# top.net
KiCad netlist of a schematic drawn in Altium Designer
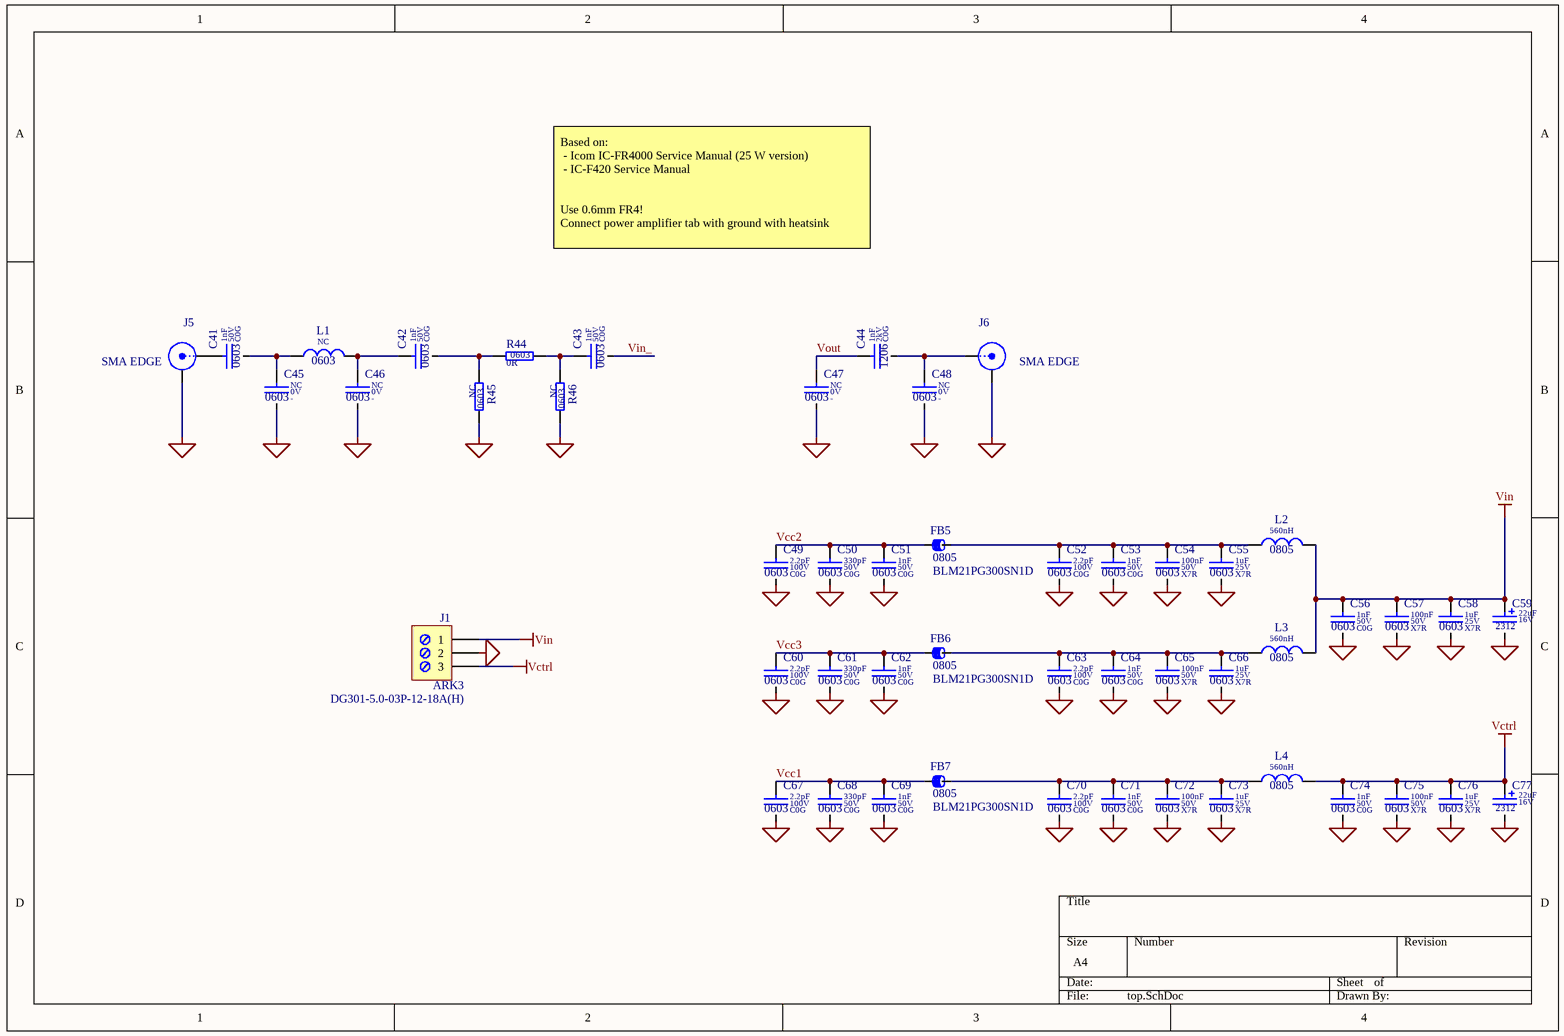
[diagram p0: top.SchDoc]

(export (version "E")
  (design (tool "Eeschema 10.0.6"))
  (components
    (comp (ref "C41")
      (value "1nF")
      (footprint "C_0603_1608")
      (description "Capacitor")
      (fields
        (field (name "DIELECTRIC") "C0G")
        (field (name "VOLTAGE") "50V")
        (field (name "SCH_FOOTPRINT") "0603")
        (field (name "PART NUMBER") "C_1nF_50V_C0G_0603_5")
        (field (name "MANUFACTURER") "Samsung")
      )
      (libsource (lib "Library") (part "C"))
    )
    (comp (ref "C42")
      (value "1nF")
      (footprint "C_0603_1608")
      (description "Capacitor")
      (fields
        (field (name "DIELECTRIC") "C0G")
        (field (name "VOLTAGE") "50V")
        (field (name "SCH_FOOTPRINT") "0603")
        (field (name "PART NUMBER") "C_1nF_50V_C0G_0603_5")
        (field (name "MANUFACTURER") "Samsung")
      )
      (libsource (lib "Library") (part "C"))
    )
    (comp (ref "C43")
      (value "1nF")
      (footprint "C_0603_1608")
      (description "Capacitor")
      (fields
        (field (name "DIELECTRIC") "C0G")
        (field (name "VOLTAGE") "50V")
        (field (name "SCH_FOOTPRINT") "0603")
        (field (name "PART NUMBER") "C_1nF_50V_C0G_0603_5")
        (field (name "MANUFACTURER") "Samsung")
      )
      (libsource (lib "Library") (part "C"))
    )
    (comp (ref "C44")
      (value "1nF")
      (footprint "C_1206_3216")
      (description "Capacitor")
      (fields
        (field (name "DIELECTRIC") "C0G")
        (field (name "VOLTAGE") "2kV")
        (field (name "SCH_FOOTPRINT") "1206")
        (field (name "PART NUMBER") "C_1nF_2kV_C0G_1206_10")
        (field (name "MANUFACTURER") "AVX")
      )
      (libsource (lib "Library") (part "C"))
    )
    (comp (ref "C45")
      (value "NC")
      (footprint "C_NC_0603_1608")
      (description "Capacitor")
      (fields
        (field (name "DIELECTRIC") "-")
        (field (name "VOLTAGE") "0V")
        (field (name "SCH_FOOTPRINT") "0603")
        (field (name "PART NUMBER") "C_GENERIC_0603")
      )
      (libsource (lib "Library") (part "C"))
    )
    (comp (ref "C46")
      (value "NC")
      (footprint "C_NC_0603_1608")
      (description "Capacitor")
      (fields
        (field (name "DIELECTRIC") "-")
        (field (name "VOLTAGE") "0V")
        (field (name "SCH_FOOTPRINT") "0603")
        (field (name "PART NUMBER") "C_GENERIC_0603")
      )
      (libsource (lib "Library") (part "C"))
    )
    (comp (ref "C47")
      (value "NC")
      (footprint "C_NC_0603_1608")
      (description "Capacitor")
      (fields
        (field (name "DIELECTRIC") "-")
        (field (name "VOLTAGE") "0V")
        (field (name "SCH_FOOTPRINT") "0603")
        (field (name "PART NUMBER") "C_GENERIC_0603")
      )
      (libsource (lib "Library") (part "C"))
    )
    (comp (ref "C48")
      (value "NC")
      (footprint "C_NC_0603_1608")
      (description "Capacitor")
      (fields
        (field (name "DIELECTRIC") "-")
        (field (name "VOLTAGE") "0V")
        (field (name "SCH_FOOTPRINT") "0603")
        (field (name "PART NUMBER") "C_GENERIC_0603")
      )
      (libsource (lib "Library") (part "C"))
    )
    (comp (ref "C49")
      (value "2.2pF")
      (footprint "C_0603_1608")
      (description "Capacitor")
      (fields
        (field (name "DIELECTRIC") "C0G")
        (field (name "VOLTAGE") "100V")
        (field (name "SCH_FOOTPRINT") "0603")
        (field (name "PART NUMBER") "C_2.2pF_100V_C0G_0603_5")
        (field (name "MANUFACTURER") "AVX")
      )
      (libsource (lib "Library") (part "C"))
    )
    (comp (ref "C50")
      (value "330pF")
      (footprint "C_0603_1608")
      (description "Capacitor")
      (fields
        (field (name "DIELECTRIC") "C0G")
        (field (name "VOLTAGE") "50V")
        (field (name "SCH_FOOTPRINT") "0603")
        (field (name "PART NUMBER") "C_330pF_50V_C0G_0603_5")
        (field (name "MANUFACTURER") "Murata")
      )
      (libsource (lib "Library") (part "C"))
    )
    (comp (ref "C51")
      (value "1nF")
      (footprint "C_0603_1608")
      (description "Capacitor")
      (fields
        (field (name "DIELECTRIC") "C0G")
        (field (name "VOLTAGE") "50V")
        (field (name "SCH_FOOTPRINT") "0603")
        (field (name "PART NUMBER") "C_1nF_50V_C0G_0603_5")
        (field (name "MANUFACTURER") "Samsung")
      )
      (libsource (lib "Library") (part "C"))
    )
    (comp (ref "C52")
      (value "2.2pF")
      (footprint "C_0603_1608")
      (description "Capacitor")
      (fields
        (field (name "DIELECTRIC") "C0G")
        (field (name "VOLTAGE") "100V")
        (field (name "SCH_FOOTPRINT") "0603")
        (field (name "PART NUMBER") "C_2.2pF_100V_C0G_0603_5")
        (field (name "MANUFACTURER") "AVX")
      )
      (libsource (lib "Library") (part "C"))
    )
    (comp (ref "C53")
      (value "1nF")
      (footprint "C_0603_1608")
      (description "Capacitor")
      (fields
        (field (name "DIELECTRIC") "C0G")
        (field (name "VOLTAGE") "50V")
        (field (name "SCH_FOOTPRINT") "0603")
        (field (name "PART NUMBER") "C_1nF_50V_C0G_0603_5")
        (field (name "MANUFACTURER") "Samsung")
      )
      (libsource (lib "Library") (part "C"))
    )
    (comp (ref "C54")
      (value "100nF")
      (footprint "C_0603_1608")
      (description "Capacitor")
      (fields
        (field (name "DIELECTRIC") "X7R")
        (field (name "VOLTAGE") "50V")
        (field (name "SCH_FOOTPRINT") "0603")
        (field (name "PART NUMBER") "C_100nF_50V_X7R_0603_5")
        (field (name "MANUFACTURER") "Samsung")
      )
      (libsource (lib "Library") (part "C"))
    )
    (comp (ref "C55")
      (value "1uF")
      (footprint "C_0603_1608")
      (description "Capacitor")
      (fields
        (field (name "DIELECTRIC") "X7R")
        (field (name "VOLTAGE") "25V")
        (field (name "SCH_FOOTPRINT") "0603")
        (field (name "PART NUMBER") "C_1uF_25V_X7R_0603_10")
        (field (name "MANUFACTURER") "Samsung")
      )
      (libsource (lib "Library") (part "C"))
    )
    (comp (ref "C56")
      (value "1nF")
      (footprint "C_0603_1608")
      (description "Capacitor")
      (fields
        (field (name "DIELECTRIC") "C0G")
        (field (name "VOLTAGE") "50V")
        (field (name "SCH_FOOTPRINT") "0603")
        (field (name "PART NUMBER") "C_1nF_50V_C0G_0603_5")
        (field (name "MANUFACTURER") "Samsung")
      )
      (libsource (lib "Library") (part "C"))
    )
    (comp (ref "C57")
      (value "100nF")
      (footprint "C_0603_1608")
      (description "Capacitor")
      (fields
        (field (name "DIELECTRIC") "X7R")
        (field (name "VOLTAGE") "50V")
        (field (name "SCH_FOOTPRINT") "0603")
        (field (name "PART NUMBER") "C_100nF_50V_X7R_0603_5")
        (field (name "MANUFACTURER") "Samsung")
      )
      (libsource (lib "Library") (part "C"))
    )
    (comp (ref "C58")
      (value "1uF")
      (footprint "C_0603_1608")
      (description "Capacitor")
      (fields
        (field (name "DIELECTRIC") "X7R")
        (field (name "VOLTAGE") "25V")
        (field (name "SCH_FOOTPRINT") "0603")
        (field (name "PART NUMBER") "C_1uF_25V_X7R_0603_10")
        (field (name "MANUFACTURER") "Samsung")
      )
      (libsource (lib "Library") (part "C"))
    )
    (comp (ref "C59")
      (value "22uF")
      (footprint "CT_2312_6032")
      (description "Capacitor")
      (fields
        (field (name "SCH_FOOTPRINT") "2312")
        (field (name "VOLTAGE") "16V")
        (field (name "PART NUMBER") "CT_22uF_16V_TA2O5_2312_10")
        (field (name "MANUFACTURER") "Kemet")
      )
      (libsource (lib "Library") (part "CT"))
    )
    (comp (ref "C60")
      (value "2.2pF")
      (footprint "C_0603_1608")
      (description "Capacitor")
      (fields
        (field (name "DIELECTRIC") "C0G")
        (field (name "VOLTAGE") "100V")
        (field (name "SCH_FOOTPRINT") "0603")
        (field (name "PART NUMBER") "C_2.2pF_100V_C0G_0603_5")
        (field (name "MANUFACTURER") "AVX")
      )
      (libsource (lib "Library") (part "C"))
    )
    (comp (ref "C61")
      (value "330pF")
      (footprint "C_0603_1608")
      (description "Capacitor")
      (fields
        (field (name "DIELECTRIC") "C0G")
        (field (name "VOLTAGE") "50V")
        (field (name "SCH_FOOTPRINT") "0603")
        (field (name "PART NUMBER") "C_330pF_50V_C0G_0603_5")
        (field (name "MANUFACTURER") "Murata")
      )
      (libsource (lib "Library") (part "C"))
    )
    (comp (ref "C62")
      (value "1nF")
      (footprint "C_0603_1608")
      (description "Capacitor")
      (fields
        (field (name "DIELECTRIC") "C0G")
        (field (name "VOLTAGE") "50V")
        (field (name "SCH_FOOTPRINT") "0603")
        (field (name "PART NUMBER") "C_1nF_50V_C0G_0603_5")
        (field (name "MANUFACTURER") "Samsung")
      )
      (libsource (lib "Library") (part "C"))
    )
    (comp (ref "C63")
      (value "2.2pF")
      (footprint "C_0603_1608")
      (description "Capacitor")
      (fields
        (field (name "DIELECTRIC") "C0G")
        (field (name "VOLTAGE") "100V")
        (field (name "SCH_FOOTPRINT") "0603")
        (field (name "PART NUMBER") "C_2.2pF_100V_C0G_0603_5")
        (field (name "MANUFACTURER") "AVX")
      )
      (libsource (lib "Library") (part "C"))
    )
    (comp (ref "C64")
      (value "1nF")
      (footprint "C_0603_1608")
      (description "Capacitor")
      (fields
        (field (name "DIELECTRIC") "C0G")
        (field (name "VOLTAGE") "50V")
        (field (name "SCH_FOOTPRINT") "0603")
        (field (name "PART NUMBER") "C_1nF_50V_C0G_0603_5")
        (field (name "MANUFACTURER") "Samsung")
      )
      (libsource (lib "Library") (part "C"))
    )
    (comp (ref "C65")
      (value "100nF")
      (footprint "C_0603_1608")
      (description "Capacitor")
      (fields
        (field (name "DIELECTRIC") "X7R")
        (field (name "VOLTAGE") "50V")
        (field (name "SCH_FOOTPRINT") "0603")
        (field (name "PART NUMBER") "C_100nF_50V_X7R_0603_5")
        (field (name "MANUFACTURER") "Samsung")
      )
      (libsource (lib "Library") (part "C"))
    )
    (comp (ref "C66")
      (value "1uF")
      (footprint "C_0603_1608")
      (description "Capacitor")
      (fields
        (field (name "DIELECTRIC") "X7R")
        (field (name "VOLTAGE") "25V")
        (field (name "SCH_FOOTPRINT") "0603")
        (field (name "PART NUMBER") "C_1uF_25V_X7R_0603_10")
        (field (name "MANUFACTURER") "Samsung")
      )
      (libsource (lib "Library") (part "C"))
    )
    (comp (ref "C67")
      (value "2.2pF")
      (footprint "C_0603_1608")
      (description "Capacitor")
      (fields
        (field (name "DIELECTRIC") "C0G")
        (field (name "VOLTAGE") "100V")
        (field (name "SCH_FOOTPRINT") "0603")
        (field (name "PART NUMBER") "C_2.2pF_100V_C0G_0603_5")
        (field (name "MANUFACTURER") "AVX")
      )
      (libsource (lib "Library") (part "C"))
    )
    (comp (ref "C68")
      (value "330pF")
      (footprint "C_0603_1608")
      (description "Capacitor")
      (fields
        (field (name "DIELECTRIC") "C0G")
        (field (name "VOLTAGE") "50V")
        (field (name "SCH_FOOTPRINT") "0603")
        (field (name "PART NUMBER") "C_330pF_50V_C0G_0603_5")
        (field (name "MANUFACTURER") "Murata")
      )
      (libsource (lib "Library") (part "C"))
    )
    (comp (ref "C69")
      (value "1nF")
      (footprint "C_0603_1608")
      (description "Capacitor")
      (fields
        (field (name "DIELECTRIC") "C0G")
        (field (name "VOLTAGE") "50V")
        (field (name "SCH_FOOTPRINT") "0603")
        (field (name "PART NUMBER") "C_1nF_50V_C0G_0603_5")
        (field (name "MANUFACTURER") "Samsung")
      )
      (libsource (lib "Library") (part "C"))
    )
    (comp (ref "C70")
      (value "2.2pF")
      (footprint "C_0603_1608")
      (description "Capacitor")
      (fields
        (field (name "DIELECTRIC") "C0G")
        (field (name "VOLTAGE") "100V")
        (field (name "SCH_FOOTPRINT") "0603")
        (field (name "PART NUMBER") "C_2.2pF_100V_C0G_0603_5")
        (field (name "MANUFACTURER") "AVX")
      )
      (libsource (lib "Library") (part "C"))
    )
    (comp (ref "C71")
      (value "1nF")
      (footprint "C_0603_1608")
      (description "Capacitor")
      (fields
        (field (name "DIELECTRIC") "C0G")
        (field (name "VOLTAGE") "50V")
        (field (name "SCH_FOOTPRINT") "0603")
        (field (name "PART NUMBER") "C_1nF_50V_C0G_0603_5")
        (field (name "MANUFACTURER") "Samsung")
      )
      (libsource (lib "Library") (part "C"))
    )
    (comp (ref "C72")
      (value "100nF")
      (footprint "C_0603_1608")
      (description "Capacitor")
      (fields
        (field (name "DIELECTRIC") "X7R")
        (field (name "VOLTAGE") "50V")
        (field (name "SCH_FOOTPRINT") "0603")
        (field (name "PART NUMBER") "C_100nF_50V_X7R_0603_5")
        (field (name "MANUFACTURER") "Samsung")
      )
      (libsource (lib "Library") (part "C"))
    )
    (comp (ref "C73")
      (value "1uF")
      (footprint "C_0603_1608")
      (description "Capacitor")
      (fields
        (field (name "DIELECTRIC") "X7R")
        (field (name "VOLTAGE") "25V")
        (field (name "SCH_FOOTPRINT") "0603")
        (field (name "PART NUMBER") "C_1uF_25V_X7R_0603_10")
        (field (name "MANUFACTURER") "Samsung")
      )
      (libsource (lib "Library") (part "C"))
    )
    (comp (ref "C74")
      (value "1nF")
      (footprint "C_0603_1608")
      (description "Capacitor")
      (fields
        (field (name "DIELECTRIC") "C0G")
        (field (name "VOLTAGE") "50V")
        (field (name "SCH_FOOTPRINT") "0603")
        (field (name "PART NUMBER") "C_1nF_50V_C0G_0603_5")
        (field (name "MANUFACTURER") "Samsung")
      )
      (libsource (lib "Library") (part "C"))
    )
    (comp (ref "C75")
      (value "100nF")
      (footprint "C_0603_1608")
      (description "Capacitor")
      (fields
        (field (name "DIELECTRIC") "X7R")
        (field (name "VOLTAGE") "50V")
        (field (name "SCH_FOOTPRINT") "0603")
        (field (name "PART NUMBER") "C_100nF_50V_X7R_0603_5")
        (field (name "MANUFACTURER") "Samsung")
      )
      (libsource (lib "Library") (part "C"))
    )
    (comp (ref "C76")
      (value "1uF")
      (footprint "C_0603_1608")
      (description "Capacitor")
      (fields
        (field (name "DIELECTRIC") "X7R")
        (field (name "VOLTAGE") "25V")
        (field (name "SCH_FOOTPRINT") "0603")
        (field (name "PART NUMBER") "C_1uF_25V_X7R_0603_10")
        (field (name "MANUFACTURER") "Samsung")
      )
      (libsource (lib "Library") (part "C"))
    )
    (comp (ref "C77")
      (value "22uF")
      (footprint "CT_2312_6032")
      (description "Capacitor")
      (fields
        (field (name "SCH_FOOTPRINT") "2312")
        (field (name "VOLTAGE") "16V")
        (field (name "PART NUMBER") "CT_22uF_16V_TA2O5_2312_10")
        (field (name "MANUFACTURER") "Kemet")
      )
      (libsource (lib "Library") (part "CT"))
    )
    (comp (ref "FB5")
      (value "BLM21PG300SN1D")
      (footprint "FB_0805_2012")
      (description "Ferrite Bead")
      (fields
        (field (name "PART NUMBER") "FB_BLM21PG300SN1D")
        (field (name "SCH_FOOTPRINT") "0805")
        (field (name "MANUFACTURER") "Murata")
      )
      (libsource (lib "Library") (part "FB"))
    )
    (comp (ref "FB6")
      (value "BLM21PG300SN1D")
      (footprint "FB_0805_2012")
      (description "Ferrite Bead")
      (fields
        (field (name "PART NUMBER") "FB_BLM21PG300SN1D")
        (field (name "SCH_FOOTPRINT") "0805")
        (field (name "MANUFACTURER") "Murata")
      )
      (libsource (lib "Library") (part "FB"))
    )
    (comp (ref "FB7")
      (value "BLM21PG300SN1D")
      (footprint "FB_0805_2012")
      (description "Ferrite Bead")
      (fields
        (field (name "PART NUMBER") "FB_BLM21PG300SN1D")
        (field (name "SCH_FOOTPRINT") "0805")
        (field (name "MANUFACTURER") "Murata")
      )
      (libsource (lib "Library") (part "FB"))
    )
    (comp (ref "J1")
      (value "DG301-5.0-03P-12-18A(H)")
      (footprint "J_ARK3")
      (description "ARK Screw terminal, 3-Pin")
      (fields
        (field (name "SCH_FOOTPRINT") "ARK3")
        (field (name "PART NUMBER") "J_TB-5.0-P-3P")
        (field (name "MANUFACTURER") "DEGSON ELECTRONICS")
      )
      (libsource (lib "Library") (part "J_ARK3"))
    )
    (comp (ref "J5")
      (value "SMA EDGE")
      (footprint "J_SMA_EDGE")
      (description "SMA connector")
      (fields (field (name "PART NUMBER") "J_SMA_EDGE_UNIVERSAL") (field (name "SCH_FOOTPRINT") "SMA EDGE"))
      (libsource (lib "Library") (part "J_SMA"))
    )
    (comp (ref "J6")
      (value "SMA EDGE")
      (footprint "J_SMA_EDGE")
      (description "SMA connector")
      (fields (field (name "PART NUMBER") "J_SMA_EDGE_UNIVERSAL") (field (name "SCH_FOOTPRINT") "SMA EDGE"))
      (libsource (lib "Library") (part "J_SMA"))
    )
    (comp (ref "L1")
      (value "NC")
      (footprint "L_NC_0603_1608")
      (description "Induction")
      (fields (field (name "SCH_FOOTPRINT") "0603") (field (name "PART NUMBER") "L_0603"))
      (libsource (lib "Library") (part "L"))
    )
    (comp (ref "L2")
      (value "560nH")
      (footprint "L_0805_2012")
      (description "Induction")
      (fields
        (field (name "SCH_FOOTPRINT") "0805")
        (field (name "PART NUMBER") "L_560nH_1.7A_0805")
        (field (name "MANUFACTURER") "Wurth")
      )
      (libsource (lib "Library") (part "L"))
    )
    (comp (ref "L3")
      (value "560nH")
      (footprint "L_0805_2012")
      (description "Induction")
      (fields
        (field (name "SCH_FOOTPRINT") "0805")
        (field (name "PART NUMBER") "L_560nH_1.7A_0805")
        (field (name "MANUFACTURER") "Wurth")
      )
      (libsource (lib "Library") (part "L"))
    )
    (comp (ref "L4")
      (value "560nH")
      (footprint "L_0805_2012")
      (description "Induction")
      (fields
        (field (name "SCH_FOOTPRINT") "0805")
        (field (name "PART NUMBER") "L_560nH_1.7A_0805")
        (field (name "MANUFACTURER") "Wurth")
      )
      (libsource (lib "Library") (part "L"))
    )
    (comp (ref "R44")
      (value "0R")
      (footprint "R_0603_1608")
      (fields
        (field (name "SCH_FOOTPRINT") "0603")
        (field (name "PART NUMBER") "R_0R_0603_5")
        (field (name "VOLTAGE") "50V")
        (field (name "POWER") "100mW")
      )
      (libsource (lib "Library") (part "R"))
    )
    (comp (ref "R45")
      (value "NC")
      (footprint "R_NC_0603_1608")
      (fields
        (field (name "SCH_FOOTPRINT") "0603")
        (field (name "PART NUMBER") "R_GENERIC_0603")
        (field (name "Comment") "Resistor")
      )
      (libsource (lib "Library") (part "R"))
    )
    (comp (ref "R46")
      (value "NC")
      (footprint "R_NC_0603_1608")
      (fields
        (field (name "SCH_FOOTPRINT") "0603")
        (field (name "PART NUMBER") "R_GENERIC_0603")
        (field (name "Comment") "Resistor")
      )
      (libsource (lib "Library") (part "R"))
    )
  )
  (nets
    (net (code "1") (name "/Vcc1") (class "Default")
      (node (ref "C67") (pin "1") (pinfunction "1_1") (pintype "passive"))
      (node (ref "C68") (pin "1") (pinfunction "1_1") (pintype "passive"))
      (node (ref "C69") (pin "1") (pinfunction "1_1") (pintype "passive"))
      (node (ref "FB7") (pin "1") (pintype "passive"))
    )
    (net (code "2") (name "/Vcc2") (class "Default")
      (node (ref "C49") (pin "1") (pinfunction "1_1") (pintype "passive"))
      (node (ref "C50") (pin "1") (pinfunction "1_1") (pintype "passive"))
      (node (ref "C51") (pin "1") (pinfunction "1_1") (pintype "passive"))
      (node (ref "FB5") (pin "1") (pintype "passive"))
    )
    (net (code "3") (name "/Vcc3") (class "Default")
      (node (ref "C60") (pin "1") (pinfunction "1_1") (pintype "passive"))
      (node (ref "C61") (pin "1") (pinfunction "1_1") (pintype "passive"))
      (node (ref "C62") (pin "1") (pinfunction "1_1") (pintype "passive"))
      (node (ref "FB6") (pin "1") (pintype "passive"))
    )
    (net (code "4") (name "/Vin_") (class "Default")
      (node (ref "C43") (pin "2") (pinfunction "2_2") (pintype "passive"))
    )
    (net (code "5") (name "/Vout") (class "Default")
      (node (ref "C44") (pin "1") (pinfunction "1_1") (pintype "passive"))
      (node (ref "C47") (pin "1") (pinfunction "1_1") (pintype "passive"))
    )
    (net (code "6") (name "GND") (class "Default")
      (node (ref "C45") (pin "2") (pinfunction "2_2") (pintype "passive"))
      (node (ref "C46") (pin "2") (pinfunction "2_2") (pintype "passive"))
      (node (ref "C47") (pin "2") (pinfunction "2_2") (pintype "passive"))
      (node (ref "C48") (pin "2") (pinfunction "2_2") (pintype "passive"))
      (node (ref "C49") (pin "2") (pinfunction "2_2") (pintype "passive"))
      (node (ref "C50") (pin "2") (pinfunction "2_2") (pintype "passive"))
      (node (ref "C51") (pin "2") (pinfunction "2_2") (pintype "passive"))
      (node (ref "C52") (pin "2") (pinfunction "2_2") (pintype "passive"))
      (node (ref "C53") (pin "2") (pinfunction "2_2") (pintype "passive"))
      (node (ref "C54") (pin "2") (pinfunction "2_2") (pintype "passive"))
      (node (ref "C55") (pin "2") (pinfunction "2_2") (pintype "passive"))
      (node (ref "C56") (pin "2") (pinfunction "2_2") (pintype "passive"))
      (node (ref "C57") (pin "2") (pinfunction "2_2") (pintype "passive"))
      (node (ref "C58") (pin "2") (pinfunction "2_2") (pintype "passive"))
      (node (ref "C59") (pin "2") (pinfunction "2_2") (pintype "passive"))
      (node (ref "C60") (pin "2") (pinfunction "2_2") (pintype "passive"))
      (node (ref "C61") (pin "2") (pinfunction "2_2") (pintype "passive"))
      (node (ref "C62") (pin "2") (pinfunction "2_2") (pintype "passive"))
      (node (ref "C63") (pin "2") (pinfunction "2_2") (pintype "passive"))
      (node (ref "C64") (pin "2") (pinfunction "2_2") (pintype "passive"))
      (node (ref "C65") (pin "2") (pinfunction "2_2") (pintype "passive"))
      (node (ref "C66") (pin "2") (pinfunction "2_2") (pintype "passive"))
      (node (ref "C67") (pin "2") (pinfunction "2_2") (pintype "passive"))
      (node (ref "C68") (pin "2") (pinfunction "2_2") (pintype "passive"))
      (node (ref "C69") (pin "2") (pinfunction "2_2") (pintype "passive"))
      (node (ref "C70") (pin "2") (pinfunction "2_2") (pintype "passive"))
      (node (ref "C71") (pin "2") (pinfunction "2_2") (pintype "passive"))
      (node (ref "C72") (pin "2") (pinfunction "2_2") (pintype "passive"))
      (node (ref "C73") (pin "2") (pinfunction "2_2") (pintype "passive"))
      (node (ref "C74") (pin "2") (pinfunction "2_2") (pintype "passive"))
      (node (ref "C75") (pin "2") (pinfunction "2_2") (pintype "passive"))
      (node (ref "C76") (pin "2") (pinfunction "2_2") (pintype "passive"))
      (node (ref "C77") (pin "2") (pinfunction "2_2") (pintype "passive"))
      (node (ref "J1") (pin "2") (pinfunction "2_2") (pintype "passive"))
      (node (ref "J5") (pin "2") (pinfunction "GND_2") (pintype "power_in"))
      (node (ref "J6") (pin "2") (pinfunction "GND_2") (pintype "power_in"))
      (node (ref "R45") (pin "2") (pinfunction "2_2") (pintype "passive"))
      (node (ref "R46") (pin "2") (pinfunction "2_2") (pintype "passive"))
    )
    (net (code "7") (name "Net-(C41-Pad2)") (class "Default")
      (node (ref "C41") (pin "2") (pinfunction "2_2") (pintype "passive"))
      (node (ref "C45") (pin "1") (pinfunction "1_1") (pintype "passive"))
      (node (ref "L1") (pin "1") (pinfunction "1_1") (pintype "passive"))
    )
    (net (code "8") (name "Net-(C42-Pad1)") (class "Default")
      (node (ref "C42") (pin "1") (pinfunction "1_1") (pintype "passive"))
      (node (ref "C46") (pin "1") (pinfunction "1_1") (pintype "passive"))
      (node (ref "L1") (pin "2") (pinfunction "2_2") (pintype "passive"))
    )
    (net (code "9") (name "Net-(C42-Pad2)") (class "Default")
      (node (ref "C42") (pin "2") (pinfunction "2_2") (pintype "passive"))
      (node (ref "R44") (pin "1") (pinfunction "1_1") (pintype "passive"))
      (node (ref "R45") (pin "1") (pinfunction "1_1") (pintype "passive"))
    )
    (net (code "10") (name "Net-(C43-Pad1)") (class "Default")
      (node (ref "C43") (pin "1") (pinfunction "1_1") (pintype "passive"))
      (node (ref "R44") (pin "2") (pinfunction "2_2") (pintype "passive"))
      (node (ref "R46") (pin "1") (pinfunction "1_1") (pintype "passive"))
    )
    (net (code "11") (name "Net-(C52-Pad1)") (class "Default")
      (node (ref "C52") (pin "1") (pinfunction "1_1") (pintype "passive"))
      (node (ref "C53") (pin "1") (pinfunction "1_1") (pintype "passive"))
      (node (ref "C54") (pin "1") (pinfunction "1_1") (pintype "passive"))
      (node (ref "C55") (pin "1") (pinfunction "1_1") (pintype "passive"))
      (node (ref "FB5") (pin "2") (pintype "passive"))
      (node (ref "L2") (pin "1") (pinfunction "1_1") (pintype "passive"))
    )
    (net (code "12") (name "Net-(C63-Pad1)") (class "Default")
      (node (ref "C63") (pin "1") (pinfunction "1_1") (pintype "passive"))
      (node (ref "C64") (pin "1") (pinfunction "1_1") (pintype "passive"))
      (node (ref "C65") (pin "1") (pinfunction "1_1") (pintype "passive"))
      (node (ref "C66") (pin "1") (pinfunction "1_1") (pintype "passive"))
      (node (ref "FB6") (pin "2") (pintype "passive"))
      (node (ref "L3") (pin "1") (pinfunction "1_1") (pintype "passive"))
    )
    (net (code "13") (name "Net-(C70-Pad1)") (class "Default")
      (node (ref "C70") (pin "1") (pinfunction "1_1") (pintype "passive"))
      (node (ref "C71") (pin "1") (pinfunction "1_1") (pintype "passive"))
      (node (ref "C72") (pin "1") (pinfunction "1_1") (pintype "passive"))
      (node (ref "C73") (pin "1") (pinfunction "1_1") (pintype "passive"))
      (node (ref "FB7") (pin "2") (pintype "passive"))
      (node (ref "L4") (pin "1") (pinfunction "1_1") (pintype "passive"))
    )
    (net (code "14") (name "Net-(J5-X)") (class "Default")
      (node (ref "C41") (pin "1") (pinfunction "1_1") (pintype "passive"))
      (node (ref "J5") (pin "1") (pinfunction "X_1") (pintype "passive"))
    )
    (net (code "15") (name "Net-(J6-X)") (class "Default")
      (node (ref "C44") (pin "2") (pinfunction "2_2") (pintype "passive"))
      (node (ref "C48") (pin "1") (pinfunction "1_1") (pintype "passive"))
      (node (ref "J6") (pin "1") (pinfunction "X_1") (pintype "passive"))
    )
    (net (code "16") (name "Vctrl") (class "Default")
      (node (ref "C74") (pin "1") (pinfunction "1_1") (pintype "passive"))
      (node (ref "C75") (pin "1") (pinfunction "1_1") (pintype "passive"))
      (node (ref "C76") (pin "1") (pinfunction "1_1") (pintype "passive"))
      (node (ref "C77") (pin "1") (pinfunction "1_1") (pintype "passive"))
      (node (ref "J1") (pin "3") (pinfunction "3_3") (pintype "passive"))
      (node (ref "L4") (pin "2") (pinfunction "2_2") (pintype "passive"))
    )
    (net (code "17") (name "Vin") (class "Default")
      (node (ref "C56") (pin "1") (pinfunction "1_1") (pintype "passive"))
      (node (ref "C57") (pin "1") (pinfunction "1_1") (pintype "passive"))
      (node (ref "C58") (pin "1") (pinfunction "1_1") (pintype "passive"))
      (node (ref "C59") (pin "1") (pinfunction "1_1") (pintype "passive"))
      (node (ref "J1") (pin "1") (pinfunction "1_1") (pintype "passive"))
      (node (ref "L2") (pin "2") (pinfunction "2_2") (pintype "passive"))
      (node (ref "L3") (pin "2") (pinfunction "2_2") (pintype "passive"))
    )
  )
)
